# ESProgrammer.net
KiCad netlist of a schematic drawn in EAGLE
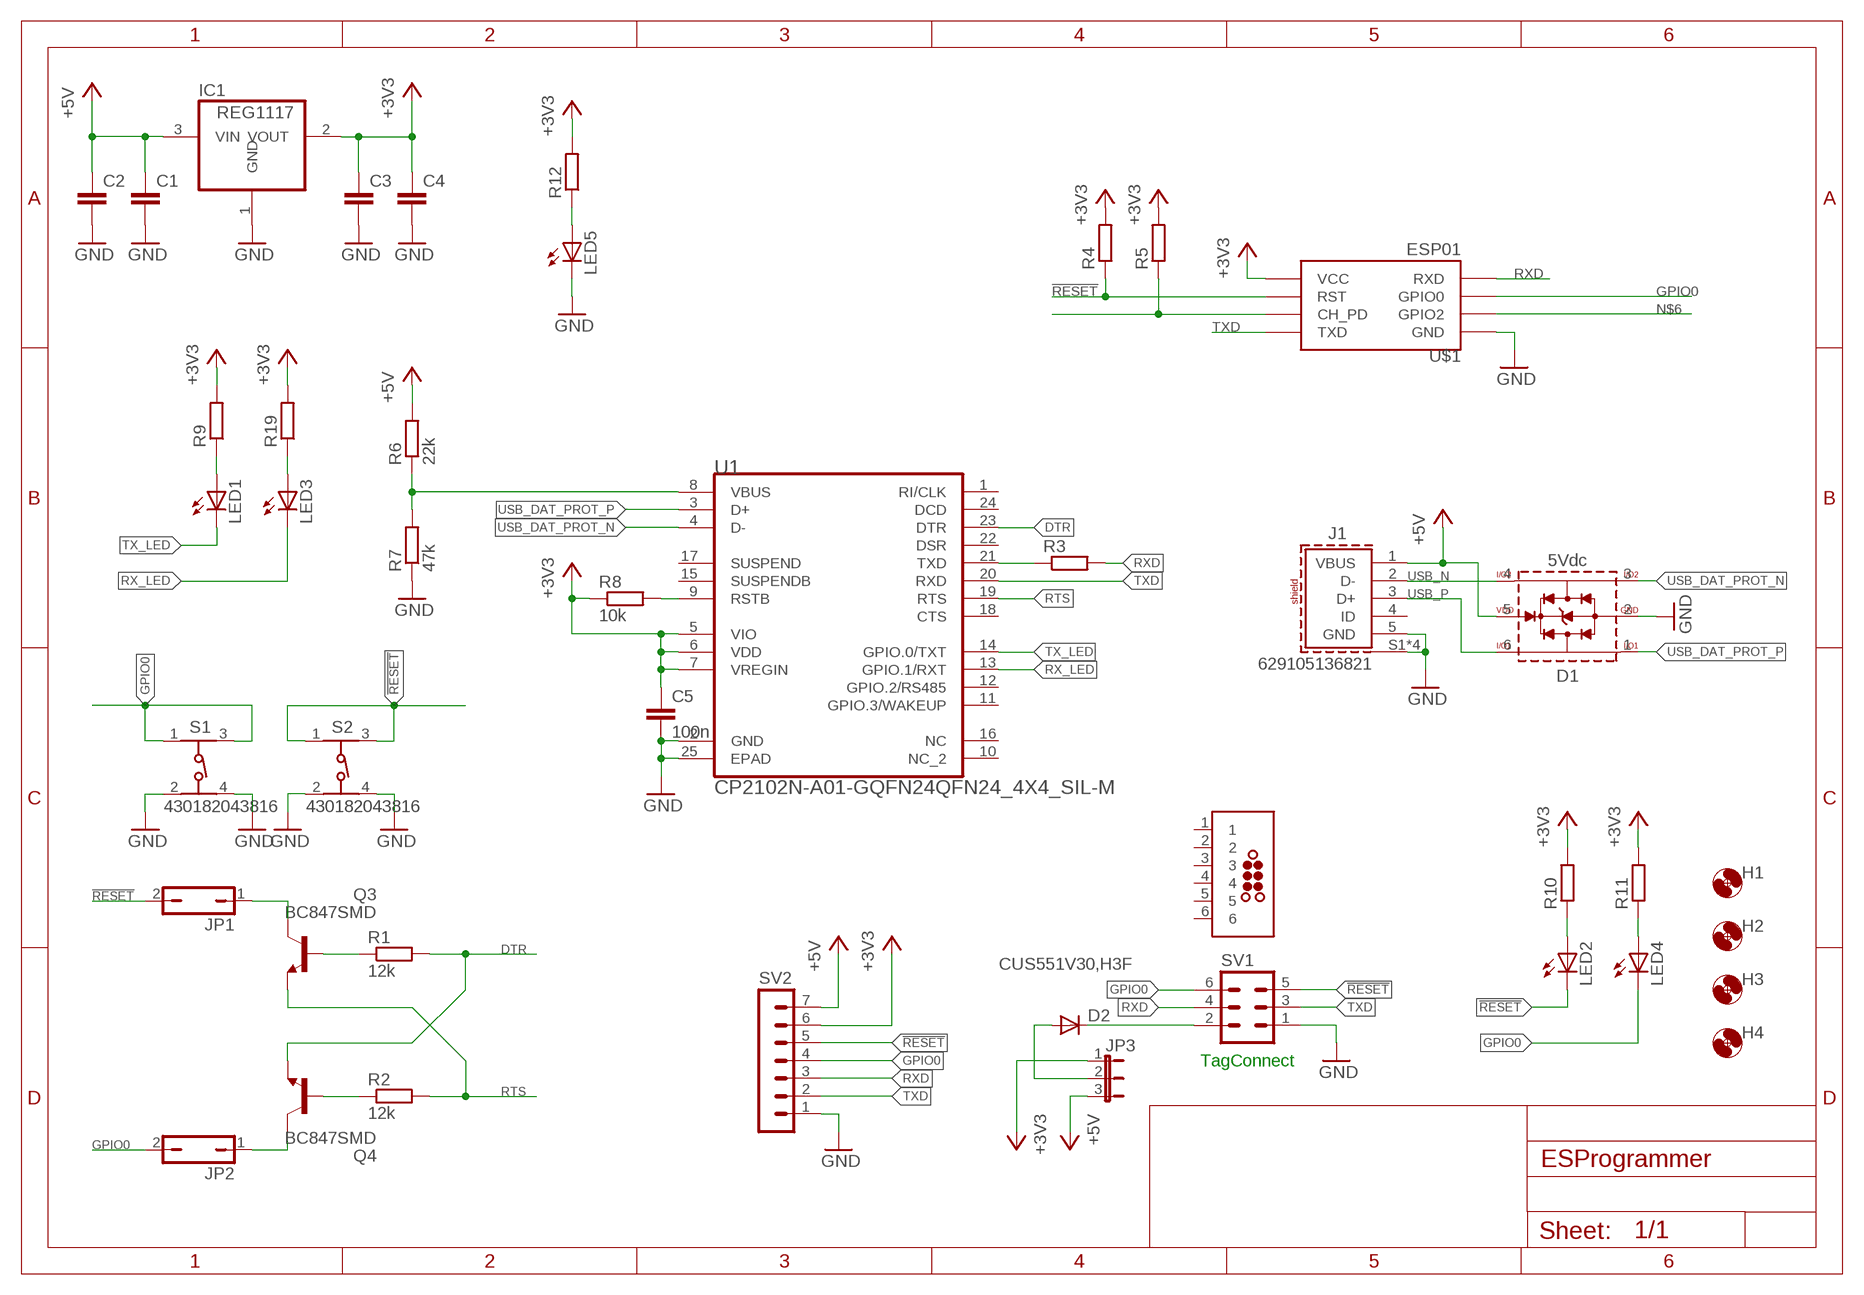
[diagram p0: schematic, sheet 1]

(export (version "E")
  (design (tool "Eeschema 10.0.6"))
  (components
    (comp (ref "C1")
      (value "C-EUC0603")
      (footprint "eagle-import:C0603")
      (libsource (lib "eagle-import") (part "C-EUC0603"))
    )
    (comp (ref "C2")
      (value "C-EUC0603")
      (footprint "eagle-import:C0603")
      (libsource (lib "eagle-import") (part "C-EUC0603"))
    )
    (comp (ref "C3")
      (value "C-EUC0603")
      (footprint "eagle-import:C0603")
      (libsource (lib "eagle-import") (part "C-EUC0603"))
    )
    (comp (ref "C4")
      (value "C-EUC0603")
      (footprint "eagle-import:C0603")
      (libsource (lib "eagle-import") (part "C-EUC0603"))
    )
    (comp (ref "C5")
      (value "100n")
      (footprint "eagle-import:C0603")
      (libsource (lib "eagle-import") (part "C-EUC0603"))
    )
    (comp (ref "D1")
      (value "5Vdc")
      (footprint "eagle-import:WE-TVS_SOT23-6L")
      (libsource (lib "eagle-import") (part "WE-TVS-HS_SOT23-6L_82400102"))
    )
    (comp (ref "D2")
      (value "CUS551V30,H3F")
      (footprint "eagle-import:SOD323-R")
      (libsource (lib "eagle-import") (part "DIODE-SOD323-R"))
    )
    (comp (ref "H1")
      (value "MOUNT-HOLE3.2")
      (footprint "eagle-import:3,2")
      (libsource (lib "eagle-import") (part "MOUNT-HOLE3.2"))
    )
    (comp (ref "H2")
      (value "MOUNT-HOLE3.2")
      (footprint "eagle-import:3,2")
      (libsource (lib "eagle-import") (part "MOUNT-HOLE3.2"))
    )
    (comp (ref "H3")
      (value "MOUNT-HOLE3.2")
      (footprint "eagle-import:3,2")
      (libsource (lib "eagle-import") (part "MOUNT-HOLE3.2"))
    )
    (comp (ref "H4")
      (value "MOUNT-HOLE3.2")
      (footprint "eagle-import:3,2")
      (libsource (lib "eagle-import") (part "MOUNT-HOLE3.2"))
    )
    (comp (ref "IC1")
      (value "REG1117")
      (footprint "eagle-import:SOT223")
      (libsource (lib "eagle-import") (part "REG1117"))
    )
    (comp (ref "J1")
      (value "629105136821")
      (footprint "eagle-import:629105136821")
      (libsource (lib "eagle-import") (part "629105136821"))
    )
    (comp (ref "J2")
      (value "TC2030-MCP-NL")
      (footprint "eagle-import:TC2030-MCP-NL")
      (libsource (lib "eagle-import") (part "TC2030-MCP-NL"))
    )
    (comp (ref "JP1")
      (value "JP1Q")
      (footprint "eagle-import:JP1")
      (libsource (lib "eagle-import") (part "JP1Q"))
    )
    (comp (ref "JP2")
      (value "JP1Q")
      (footprint "eagle-import:JP1")
      (libsource (lib "eagle-import") (part "JP1Q"))
    )
    (comp (ref "JP3")
      (value "JP2E")
      (footprint "eagle-import:JP2")
      (libsource (lib "eagle-import") (part "JP2E"))
    )
    (comp (ref "LED1")
      (value "LEDCHIP-LED0603")
      (footprint "eagle-import:CHIP-LED0603")
      (libsource (lib "eagle-import") (part "LEDCHIP-LED0603"))
    )
    (comp (ref "LED2")
      (value "LEDCHIP-LED0603")
      (footprint "eagle-import:CHIP-LED0603")
      (libsource (lib "eagle-import") (part "LEDCHIP-LED0603"))
    )
    (comp (ref "LED3")
      (value "LEDCHIP-LED0603")
      (footprint "eagle-import:CHIP-LED0603")
      (libsource (lib "eagle-import") (part "LEDCHIP-LED0603"))
    )
    (comp (ref "LED4")
      (value "LEDCHIP-LED0603")
      (footprint "eagle-import:CHIP-LED0603")
      (libsource (lib "eagle-import") (part "LEDCHIP-LED0603"))
    )
    (comp (ref "LED5")
      (value "LEDCHIP-LED0603")
      (footprint "eagle-import:CHIP-LED0603")
      (libsource (lib "eagle-import") (part "LEDCHIP-LED0603"))
    )
    (comp (ref "Q3")
      (value "BC847SMD")
      (footprint "eagle-import:SOT23")
      (libsource (lib "eagle-import") (part "BC847SMD"))
    )
    (comp (ref "Q4")
      (value "BC847SMD")
      (footprint "eagle-import:SOT23")
      (libsource (lib "eagle-import") (part "BC847SMD"))
    )
    (comp (ref "R1")
      (value "12k")
      (footprint "eagle-import:R0603")
      (libsource (lib "eagle-import") (part "R-EU_R0603"))
    )
    (comp (ref "R2")
      (value "12k")
      (footprint "eagle-import:R0603")
      (libsource (lib "eagle-import") (part "R-EU_R0603"))
    )
    (comp (ref "R3")
      (value "R-EU_R0603")
      (footprint "eagle-import:R0603")
      (libsource (lib "eagle-import") (part "R-EU_R0603"))
    )
    (comp (ref "R4")
      (value "R-EU_R0603")
      (footprint "eagle-import:R0603")
      (libsource (lib "eagle-import") (part "R-EU_R0603"))
    )
    (comp (ref "R5")
      (value "R-EU_R0603")
      (footprint "eagle-import:R0603")
      (libsource (lib "eagle-import") (part "R-EU_R0603"))
    )
    (comp (ref "R6")
      (value "22k")
      (footprint "eagle-import:R0603")
      (libsource (lib "eagle-import") (part "R-EU_R0603"))
    )
    (comp (ref "R7")
      (value "47k")
      (footprint "eagle-import:R0603")
      (libsource (lib "eagle-import") (part "R-EU_R0603"))
    )
    (comp (ref "R8")
      (value "10k")
      (footprint "eagle-import:R0603")
      (libsource (lib "eagle-import") (part "R-EU_R0603"))
    )
    (comp (ref "R9")
      (value "R-EU_R0603")
      (footprint "eagle-import:R0603")
      (libsource (lib "eagle-import") (part "R-EU_R0603"))
    )
    (comp (ref "R10")
      (value "R-EU_R0603")
      (footprint "eagle-import:R0603")
      (libsource (lib "eagle-import") (part "R-EU_R0603"))
    )
    (comp (ref "R11")
      (value "R-EU_R0603")
      (footprint "eagle-import:R0603")
      (libsource (lib "eagle-import") (part "R-EU_R0603"))
    )
    (comp (ref "R12")
      (value "R-EU_R0603")
      (footprint "eagle-import:R0603")
      (libsource (lib "eagle-import") (part "R-EU_R0603"))
    )
    (comp (ref "R19")
      (value "R-EU_R0603")
      (footprint "eagle-import:R0603")
      (libsource (lib "eagle-import") (part "R-EU_R0603"))
    )
    (comp (ref "S1")
      (value "430182043816")
      (footprint "eagle-import:430182043816")
      (libsource (lib "eagle-import") (part "430182043816"))
    )
    (comp (ref "S2")
      (value "430182043816")
      (footprint "eagle-import:430182043816")
      (libsource (lib "eagle-import") (part "430182043816"))
    )
    (comp (ref "SV1")
      (value "ML6")
      (footprint "eagle-import:ML6")
      (libsource (lib "eagle-import") (part "ML6"))
    )
    (comp (ref "SV2")
      (value "MA07-1")
      (footprint "eagle-import:MA07-1")
      (libsource (lib "eagle-import") (part "MA07-1"))
    )
    (comp (ref "U$1")
      (value "ESP01")
      (footprint "eagle-import:ESP01")
      (libsource (lib "eagle-import") (part "ESP01"))
    )
    (comp (ref "U1")
      (value "CP2102N-A01-GQFN24QFN24_4X4_SIL-M")
      (footprint "eagle-import:QFN24_4X4_SIL-M")
      (fields
        (field (name "MANUFACTURER_PART_NUMBER") "CP2102N-A01-GQFN24")
        (field (name "COPYRIGHT") "Copyright (C) 2021 Ultra Librarian. All rights reserved.")
      )
      (libsource (lib "eagle-import") (part "CP2102N-A01-GQFN24QFN24_4X4_SIL-M"))
    )
  )
  (nets
    (net (code "1") (name "+3V3") (class "Default")
      (node (ref "C3") (pin "1") (pinfunction "1_1") (pintype "passive"))
      (node (ref "C4") (pin "1") (pinfunction "1_1") (pintype "passive"))
      (node (ref "C5") (pin "1") (pinfunction "1_1") (pintype "passive"))
      (node (ref "IC1") (pin "2") (pinfunction "VOUT_2") (pintype "output"))
      (node (ref "JP3") (pin "1") (pinfunction "1_1") (pintype "passive"))
      (node (ref "R10") (pin "2") (pinfunction "2_2") (pintype "passive"))
      (node (ref "R11") (pin "2") (pinfunction "2_2") (pintype "passive"))
      (node (ref "R12") (pin "2") (pinfunction "2_2") (pintype "passive"))
      (node (ref "R19") (pin "2") (pinfunction "2_2") (pintype "passive"))
      (node (ref "R4") (pin "2") (pinfunction "2_2") (pintype "passive"))
      (node (ref "R5") (pin "2") (pinfunction "2_2") (pintype "passive"))
      (node (ref "R8") (pin "1") (pinfunction "1_1") (pintype "passive"))
      (node (ref "R9") (pin "2") (pinfunction "2_2") (pintype "passive"))
      (node (ref "SV2") (pin "6") (pinfunction "6_6") (pintype "passive"))
      (node (ref "U$1") (pin "VCC") (pinfunction "VCC_VCC") (pintype "bidirectional"))
      (node (ref "U1") (pin "5") (pinfunction "VIO_5") (pintype "bidirectional"))
      (node (ref "U1") (pin "6") (pinfunction "VDD_6") (pintype "power_in"))
      (node (ref "U1") (pin "7") (pinfunction "VREGIN_7") (pintype "input"))
    )
    (net (code "2") (name "+5V") (class "Default")
      (node (ref "C1") (pin "1") (pinfunction "1_1") (pintype "passive"))
      (node (ref "C2") (pin "1") (pinfunction "1_1") (pintype "passive"))
      (node (ref "D1") (pin "5") (pinfunction "VDD_5") (pintype "passive"))
      (node (ref "IC1") (pin "3") (pinfunction "VIN_3") (pintype "input"))
      (node (ref "J1") (pin "1") (pinfunction "VBUS_1") (pintype "passive"))
      (node (ref "JP3") (pin "3") (pinfunction "3_3") (pintype "passive"))
      (node (ref "R6") (pin "2") (pinfunction "2_2") (pintype "passive"))
      (node (ref "SV2") (pin "7") (pinfunction "7_7") (pintype "passive"))
    )
    (net (code "3") (name "/2") (class "Default")
      (node (ref "J2") (pin "2") (pinfunction "2_2") (pintype "power_in"))
    )
    (net (code "4") (name "/3") (class "Default")
      (node (ref "J2") (pin "3") (pinfunction "3_3") (pintype "power_in"))
    )
    (net (code "5") (name "/N$6") (class "Default")
      (node (ref "U$1") (pin "GPIO2") (pinfunction "GPIO2_GPIO2") (pintype "bidirectional"))
    )
    (net (code "6") (name "/USB_N") (class "Default")
      (node (ref "D1") (pin "4") (pinfunction "I/O4_4") (pintype "passive"))
      (node (ref "J1") (pin "2") (pinfunction "D-_2") (pintype "passive"))
    )
    (net (code "7") (name "/USB_P") (class "Default")
      (node (ref "D1") (pin "6") (pinfunction "I/O3_6") (pintype "passive"))
      (node (ref "J1") (pin "3") (pinfunction "D+_3") (pintype "passive"))
    )
    (net (code "8") (name "/~{RESET}") (class "Default")
      (node (ref "JP1") (pin "2") (pinfunction "2_2") (pintype "passive"))
      (node (ref "LED2") (pin "C") (pinfunction "C_C") (pintype "passive"))
      (node (ref "R4") (pin "1") (pinfunction "1_1") (pintype "passive"))
      (node (ref "S2") (pin "1") (pinfunction "1_1") (pintype "passive"))
      (node (ref "S2") (pin "3") (pinfunction "3_3") (pintype "passive"))
      (node (ref "SV1") (pin "5") (pinfunction "5_5") (pintype "passive"))
      (node (ref "SV2") (pin "5") (pinfunction "5_5") (pintype "passive"))
      (node (ref "U$1") (pin "RST") (pinfunction "RST_RST") (pintype "bidirectional"))
    )
    (net (code "9") (name "DTR") (class "Default")
      (node (ref "Q4") (pin "2") (pinfunction "E_2") (pintype "passive"))
      (node (ref "R1") (pin "2") (pinfunction "2_2") (pintype "passive"))
      (node (ref "U1") (pin "23") (pinfunction "DTR_23") (pintype "output"))
    )
    (net (code "10") (name "GND") (class "Default")
      (node (ref "C1") (pin "2") (pinfunction "2_2") (pintype "passive"))
      (node (ref "C2") (pin "2") (pinfunction "2_2") (pintype "passive"))
      (node (ref "C3") (pin "2") (pinfunction "2_2") (pintype "passive"))
      (node (ref "C4") (pin "2") (pinfunction "2_2") (pintype "passive"))
      (node (ref "C5") (pin "2") (pinfunction "2_2") (pintype "passive"))
      (node (ref "D1") (pin "2") (pinfunction "GND_2") (pintype "passive"))
      (node (ref "IC1") (pin "1") (pinfunction "GND_1") (pintype "power_in"))
      (node (ref "J1") (pin "5") (pinfunction "GND_5") (pintype "passive"))
      (node (ref "J1") (pin "S1") (pinfunction "SHIELD_S1") (pintype "passive"))
      (node (ref "J1") (pin "S2") (pinfunction "SHIELD_S2") (pintype "passive"))
      (node (ref "J1") (pin "S3") (pinfunction "SHIELD_S3") (pintype "passive"))
      (node (ref "J1") (pin "S4") (pinfunction "SHIELD_S4") (pintype "passive"))
      (node (ref "LED5") (pin "C") (pinfunction "C_C") (pintype "passive"))
      (node (ref "R7") (pin "1") (pinfunction "1_1") (pintype "passive"))
      (node (ref "S1") (pin "2") (pinfunction "2_2") (pintype "passive"))
      (node (ref "S1") (pin "4") (pinfunction "4_4") (pintype "passive"))
      (node (ref "S2") (pin "2") (pinfunction "2_2") (pintype "passive"))
      (node (ref "S2") (pin "4") (pinfunction "4_4") (pintype "passive"))
      (node (ref "SV1") (pin "1") (pinfunction "1_1") (pintype "passive"))
      (node (ref "SV2") (pin "1") (pinfunction "1_1") (pintype "passive"))
      (node (ref "U$1") (pin "GND") (pinfunction "GND_GND") (pintype "bidirectional"))
      (node (ref "U1") (pin "2") (pinfunction "GND_2") (pintype "power_in"))
      (node (ref "U1") (pin "25") (pinfunction "EPAD_25") (pintype "passive"))
    )
    (net (code "11") (name "GPIO0") (class "Default")
      (node (ref "JP2") (pin "2") (pinfunction "2_2") (pintype "passive"))
      (node (ref "LED4") (pin "C") (pinfunction "C_C") (pintype "passive"))
      (node (ref "S1") (pin "1") (pinfunction "1_1") (pintype "passive"))
      (node (ref "S1") (pin "3") (pinfunction "3_3") (pintype "passive"))
      (node (ref "SV1") (pin "6") (pinfunction "6_6") (pintype "passive"))
      (node (ref "SV2") (pin "4") (pinfunction "4_4") (pintype "passive"))
      (node (ref "U$1") (pin "GPIO0") (pinfunction "GPIO0_GPIO0") (pintype "bidirectional"))
    )
    (net (code "12") (name "Net-(D2-PadA)") (class "Default")
      (node (ref "D2") (pin "A") (pinfunction "A_A") (pintype "passive"))
      (node (ref "JP3") (pin "2") (pinfunction "2_2") (pintype "passive"))
    )
    (net (code "13") (name "Net-(D2-PadC)") (class "Default")
      (node (ref "D2") (pin "C") (pinfunction "C_C") (pintype "passive"))
      (node (ref "SV1") (pin "2") (pinfunction "2_2") (pintype "passive"))
    )
    (net (code "14") (name "Net-(LED1-PadA)") (class "Default")
      (node (ref "LED1") (pin "A") (pinfunction "A_A") (pintype "passive"))
      (node (ref "R9") (pin "1") (pinfunction "1_1") (pintype "passive"))
    )
    (net (code "15") (name "Net-(LED2-PadA)") (class "Default")
      (node (ref "LED2") (pin "A") (pinfunction "A_A") (pintype "passive"))
      (node (ref "R10") (pin "1") (pinfunction "1_1") (pintype "passive"))
    )
    (net (code "16") (name "Net-(LED3-PadA)") (class "Default")
      (node (ref "LED3") (pin "A") (pinfunction "A_A") (pintype "passive"))
      (node (ref "R19") (pin "1") (pinfunction "1_1") (pintype "passive"))
    )
    (net (code "17") (name "Net-(LED4-PadA)") (class "Default")
      (node (ref "LED4") (pin "A") (pinfunction "A_A") (pintype "passive"))
      (node (ref "R11") (pin "1") (pinfunction "1_1") (pintype "passive"))
    )
    (net (code "18") (name "Net-(LED5-PadA)") (class "Default")
      (node (ref "LED5") (pin "A") (pinfunction "A_A") (pintype "passive"))
      (node (ref "R12") (pin "1") (pinfunction "1_1") (pintype "passive"))
    )
    (net (code "19") (name "Net-(Q3-B)") (class "Default")
      (node (ref "Q3") (pin "1") (pinfunction "B_1") (pintype "passive"))
      (node (ref "R1") (pin "1") (pinfunction "1_1") (pintype "passive"))
    )
    (net (code "20") (name "Net-(Q3-C)") (class "Default")
      (node (ref "JP1") (pin "1") (pinfunction "1_1") (pintype "passive"))
      (node (ref "Q3") (pin "3") (pinfunction "C_3") (pintype "passive"))
    )
    (net (code "21") (name "Net-(Q4-B)") (class "Default")
      (node (ref "Q4") (pin "1") (pinfunction "B_1") (pintype "passive"))
      (node (ref "R2") (pin "1") (pinfunction "1_1") (pintype "passive"))
    )
    (net (code "22") (name "Net-(Q4-C)") (class "Default")
      (node (ref "JP2") (pin "1") (pinfunction "1_1") (pintype "passive"))
      (node (ref "Q4") (pin "3") (pinfunction "C_3") (pintype "passive"))
    )
    (net (code "23") (name "Net-(R5-Pad1)") (class "Default")
      (node (ref "R5") (pin "1") (pinfunction "1_1") (pintype "passive"))
      (node (ref "U$1") (pin "CH_PD") (pinfunction "CH_PD_CH_PD") (pintype "bidirectional"))
    )
    (net (code "24") (name "Net-(U1-RSTB)") (class "Default")
      (node (ref "R8") (pin "2") (pinfunction "2_2") (pintype "passive"))
      (node (ref "U1") (pin "9") (pinfunction "RSTB_9") (pintype "passive"))
    )
    (net (code "25") (name "Net-(U1-TXD)") (class "Default")
      (node (ref "R3") (pin "1") (pinfunction "1_1") (pintype "passive"))
      (node (ref "U1") (pin "21") (pinfunction "TXD_21") (pintype "output"))
    )
    (net (code "26") (name "Net-(U1-VBUS)") (class "Default")
      (node (ref "R6") (pin "1") (pinfunction "1_1") (pintype "passive"))
      (node (ref "R7") (pin "2") (pinfunction "2_2") (pintype "passive"))
      (node (ref "U1") (pin "8") (pinfunction "VBUS_8") (pintype "input"))
    )
    (net (code "27") (name "RTS") (class "Default")
      (node (ref "Q3") (pin "2") (pinfunction "E_2") (pintype "passive"))
      (node (ref "R2") (pin "2") (pinfunction "2_2") (pintype "passive"))
      (node (ref "U1") (pin "19") (pinfunction "RTS_19") (pintype "output"))
    )
    (net (code "28") (name "RXD") (class "Default")
      (node (ref "R3") (pin "2") (pinfunction "2_2") (pintype "passive"))
      (node (ref "SV1") (pin "4") (pinfunction "4_4") (pintype "passive"))
      (node (ref "SV2") (pin "3") (pinfunction "3_3") (pintype "passive"))
      (node (ref "U$1") (pin "RX") (pinfunction "RXD_RX") (pintype "bidirectional"))
    )
    (net (code "29") (name "RX_LED") (class "Default")
      (node (ref "LED3") (pin "C") (pinfunction "C_C") (pintype "passive"))
      (node (ref "U1") (pin "13") (pinfunction "GPIO.1/RXT_13") (pintype "bidirectional"))
    )
    (net (code "30") (name "TXD") (class "Default")
      (node (ref "SV1") (pin "3") (pinfunction "3_3") (pintype "passive"))
      (node (ref "SV2") (pin "2") (pinfunction "2_2") (pintype "passive"))
      (node (ref "U$1") (pin "TX") (pinfunction "TXD_TX") (pintype "bidirectional"))
      (node (ref "U1") (pin "20") (pinfunction "RXD_20") (pintype "input"))
    )
    (net (code "31") (name "TX_LED") (class "Default")
      (node (ref "LED1") (pin "C") (pinfunction "C_C") (pintype "passive"))
      (node (ref "U1") (pin "14") (pinfunction "GPIO.0/TXT_14") (pintype "bidirectional"))
    )
    (net (code "32") (name "USB_DAT_PROT_N") (class "Default")
      (node (ref "D1") (pin "3") (pinfunction "I/O2_3") (pintype "passive"))
      (node (ref "U1") (pin "4") (pinfunction "D-_4") (pintype "passive"))
    )
    (net (code "33") (name "USB_DAT_PROT_P") (class "Default")
      (node (ref "D1") (pin "1") (pinfunction "I/O1_1") (pintype "passive"))
      (node (ref "U1") (pin "3") (pinfunction "D+_3") (pintype "passive"))
    )
    (net (code "34") (name "unconnected-(J1-ID-Pad4)") (class "Default")
      (node (ref "J1") (pin "4") (pinfunction "ID_4") (pintype "passive"))
    )
    (net (code "35") (name "unconnected-(J2-Pad1)") (class "Default")
      (node (ref "J2") (pin "1") (pinfunction "1_1") (pintype "passive"))
    )
    (net (code "36") (name "unconnected-(J2-Pad4)") (class "Default")
      (node (ref "J2") (pin "4") (pinfunction "4_4") (pintype "bidirectional"))
    )
    (net (code "37") (name "unconnected-(J2-Pad5)") (class "Default")
      (node (ref "J2") (pin "5") (pinfunction "5_5") (pintype "output"))
    )
    (net (code "38") (name "unconnected-(J2-Pad6)") (class "Default")
      (node (ref "J2") (pin "6") (pinfunction "6_6") (pintype "bidirectional"))
    )
    (net (code "39") (name "unconnected-(U1-CTS-Pad18)") (class "Default")
      (node (ref "U1") (pin "18") (pinfunction "CTS_18") (pintype "input"))
    )
    (net (code "40") (name "unconnected-(U1-DCD-Pad24)") (class "Default")
      (node (ref "U1") (pin "24") (pinfunction "DCD_24") (pintype "input"))
    )
    (net (code "41") (name "unconnected-(U1-DSR-Pad22)") (class "Default")
      (node (ref "U1") (pin "22") (pinfunction "DSR_22") (pintype "input"))
    )
    (net (code "42") (name "unconnected-(U1-GPIO.2{slash}RS485-Pad12)") (class "Default")
      (node (ref "U1") (pin "12") (pinfunction "GPIO.2/RS485_12") (pintype "bidirectional"))
    )
    (net (code "43") (name "unconnected-(U1-GPIO.3{slash}WAKEUP-Pad11)") (class "Default")
      (node (ref "U1") (pin "11") (pinfunction "GPIO.3/WAKEUP_11") (pintype "bidirectional"))
    )
    (net (code "44") (name "unconnected-(U1-NC-Pad16)") (class "Default")
      (node (ref "U1") (pin "16") (pinfunction "NC_16") (pintype "no_connect"))
    )
    (net (code "45") (name "unconnected-(U1-NC_2-Pad10)") (class "Default")
      (node (ref "U1") (pin "10") (pinfunction "NC_2_10") (pintype "no_connect"))
    )
    (net (code "46") (name "unconnected-(U1-RI{slash}CLK-Pad1)") (class "Default")
      (node (ref "U1") (pin "1") (pinfunction "RI/CLK_1") (pintype "bidirectional"))
    )
    (net (code "47") (name "unconnected-(U1-SUSPEND-Pad17)") (class "Default")
      (node (ref "U1") (pin "17") (pinfunction "SUSPEND_17") (pintype "output"))
    )
    (net (code "48") (name "unconnected-(U1-SUSPENDB-Pad15)") (class "Default")
      (node (ref "U1") (pin "15") (pinfunction "SUSPENDB_15") (pintype "output"))
    )
  )
)
